# MCU.net
KiCad netlist of a schematic drawn in Altium Designer
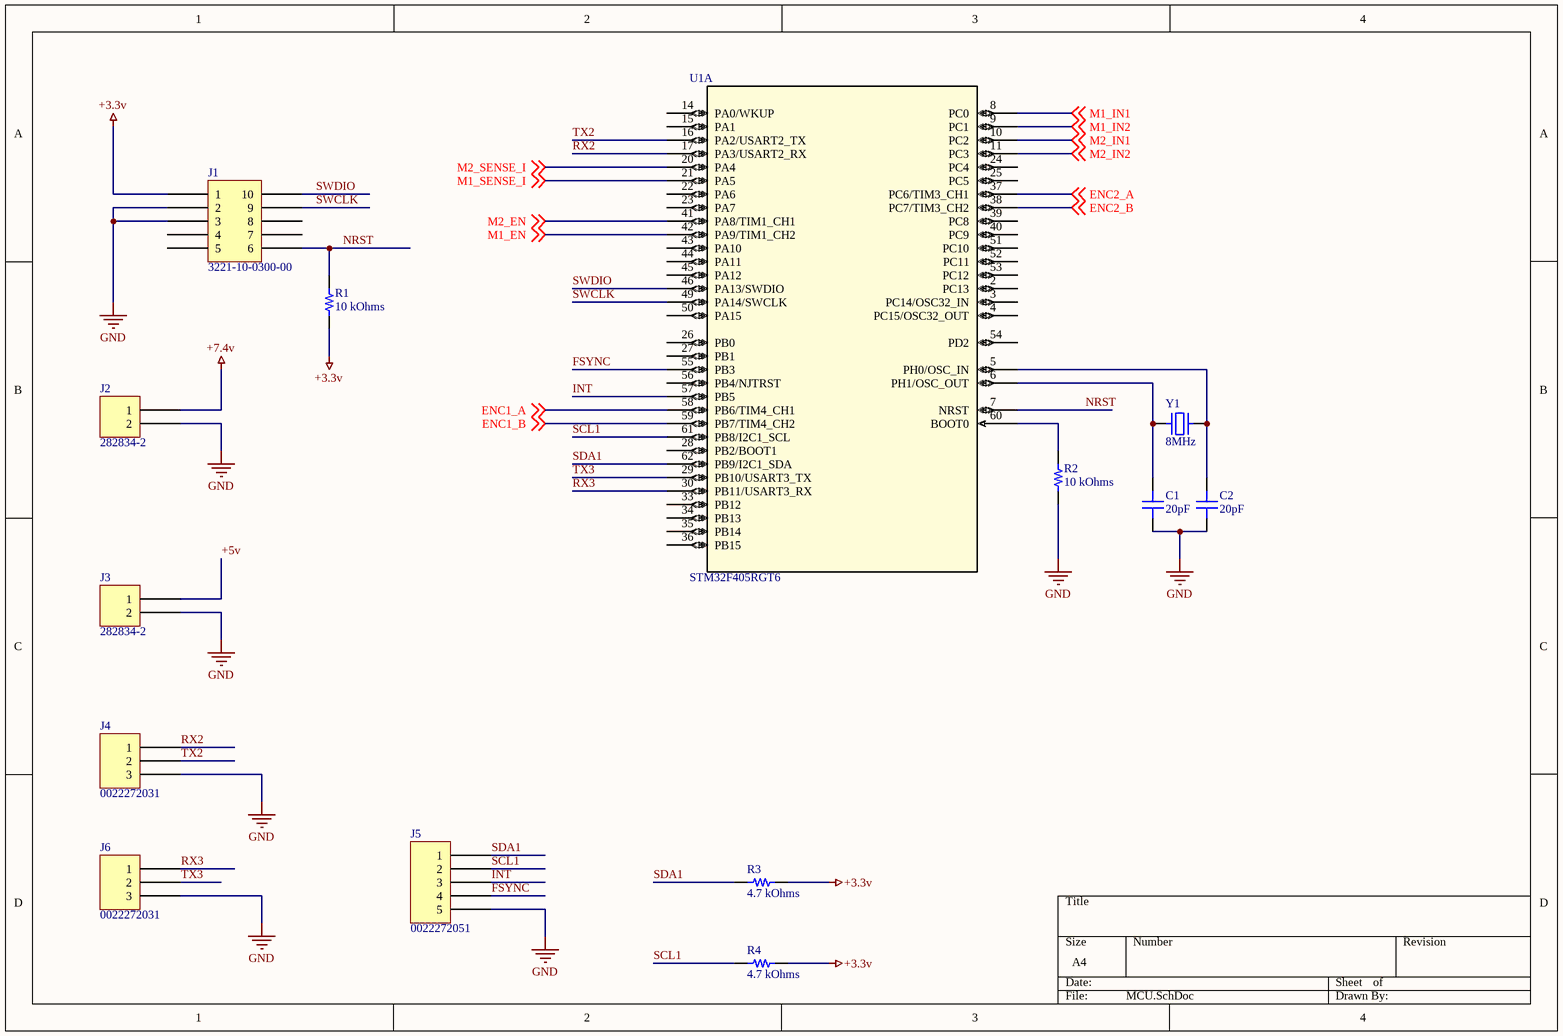
[diagram p0: MCU.SchDoc]

(export (version "E")
  (design (tool "Eeschema 10.0.6"))
  (components
    (comp (ref "C1")
      (value "20pF")
      (footprint "CAP 0805_2012")
      (description "CAP CER 20PF 16V C0G/NP0 0805")
      (fields (field (name "PART NUMBER") "C0805C200J4GAC7800") (field (name "MANUFACTURER") "KEMET"))
      (libsource (lib "Celestial Altium Library - altium_library") (part "Capacitor"))
    )
    (comp (ref "C2")
      (value "20pF")
      (footprint "CAP 0805_2012")
      (description "CAP CER 20PF 16V C0G/NP0 0805")
      (fields (field (name "PART NUMBER") "C0805C200J4GAC7800") (field (name "MANUFACTURER") "KEMET"))
      (libsource (lib "Celestial Altium Library - altium_library") (part "Capacitor"))
    )
    (comp (ref "J1")
      (value "3221-10-0300-00")
      (footprint "CNC TECH 3221-10-0300-00")
      (description "CONN HEADER SMD 10POS 1.27MM")
      (fields (field (name "MANUFACTURER") "CNC Tech"))
      (libsource (lib "Celestial Altium Library - altium_library") (part "2x5 Pin"))
    )
    (comp (ref "J2")
      (value "282834-2")
      (footprint "TE 282834-2")
      (description "TERM BLK 2P SIDE ENT 2.54MM PCB")
      (fields (field (name "MANUFACTURER") "TE Connectivity AMP Connectors") (field (name "VOLTAGE") "150V"))
      (libsource (lib "Celestial Altium Library - altium_library") (part "2 Pin"))
    )
    (comp (ref "J3")
      (value "282834-2")
      (footprint "TE 282834-2")
      (description "TERM BLK 2P SIDE ENT 2.54MM PCB")
      (fields (field (name "MANUFACTURER") "TE Connectivity AMP Connectors") (field (name "VOLTAGE") "150V"))
      (libsource (lib "Celestial Altium Library - altium_library") (part "2 Pin"))
    )
    (comp (ref "J4")
      (value "0022272031")
      (footprint "MOLEX KK 0022272031")
      (description "CONN HEADER VERT 3POS 2.54MM")
      (fields (field (name "MANUFACTURER") "Molex"))
      (libsource (lib "Celestial Altium Library - altium_library") (part "3 Pin"))
    )
    (comp (ref "J5")
      (value "0022272051")
      (footprint "MOLEX KK 0022272051")
      (description "CONN HEADER VERT 5POS 2.54MM")
      (fields (field (name "MANUFACTURER") "Molex"))
      (libsource (lib "Celestial Altium Library - altium_library") (part "5 Pin"))
    )
    (comp (ref "J6")
      (value "0022272031")
      (footprint "MOLEX KK 0022272031")
      (description "CONN HEADER VERT 3POS 2.54MM")
      (fields (field (name "MANUFACTURER") "Molex"))
      (libsource (lib "Celestial Altium Library - altium_library") (part "3 Pin"))
    )
    (comp (ref "R1")
      (value "10 kOhms")
      (footprint "RES 0805_2012")
      (description "RES 10K OHM 5% 1/8W 0805")
      (fields
        (field (name "PART NUMBER") "RMCS0805JT10K0")
        (field (name "MANUFACTURER") "Stackpole Electronics Inc")
      )
      (libsource (lib "Celestial Altium Library - altium_library") (part "Resistor"))
    )
    (comp (ref "R2")
      (value "10 kOhms")
      (footprint "RES 0805_2012")
      (description "RES SMD 10K OHM 5% 1/8W 0805")
      (fields (field (name "PART NUMBER") "RC0805JR-0710KL") (field (name "MANUFACTURER") "Yageo"))
      (libsource (lib "Celestial Altium Library - altium_library") (part "Resistor"))
    )
    (comp (ref "R3")
      (value "4.7 kOhms")
      (footprint "RES 0805_2012")
      (description "RES SMD 4.7K OHM 5% 1/8W 0805")
      (fields (field (name "PART NUMBER") "CRCW08054K70JNTA") (field (name "MANUFACTURER") "Vishay Dale"))
      (libsource (lib "Celestial Altium Library - altium_library") (part "Resistor"))
    )
    (comp (ref "R4")
      (value "4.7 kOhms")
      (footprint "RES 0805_2012")
      (description "RES SMD 4.7K OHM 5% 1/8W 0805")
      (fields (field (name "PART NUMBER") "CRCW08054K70JNTA") (field (name "MANUFACTURER") "Vishay Dale"))
      (libsource (lib "Celestial Altium Library - altium_library") (part "Resistor"))
    )
    (comp (ref "U1")
      (value "STM32F405RGT6")
      (footprint "LQFP64-10x10mm")
      (description "No Description Available")
      (fields (field (name "COPYRIGHT") "Copyright (C) 2018 Accelerated Designs. All rights reserved"))
      (libsource (lib "STM32F405RGT6") (part "STM32F405RGT6"))
    )
    (comp (ref "Y1")
      (value "8MHz")
      (footprint "NDK NX5032GA")
      (description "CRYSTAL 8MHZ 18PF SMD")
      (fields
        (field (name "PART NUMBER") "NX5032GA-8MHZ-EXS00A-CG07039")
        (field (name "MANUFACTURER") "NDK America, Inc.")
      )
      (libsource (lib "Celestial Altium Library - altium_library") (part "NDK Crystal NX5032GA"))
    )
  )
  (nets
    (net (code "1") (name "+3.3v") (class "Default")
      (node (ref "J1") (pin "1") (pinfunction "1_1") (pintype "passive"))
      (node (ref "R1") (pin "2") (pinfunction "2_2") (pintype "passive"))
      (node (ref "R3") (pin "2") (pinfunction "2_2") (pintype "passive"))
      (node (ref "R4") (pin "2") (pinfunction "2_2") (pintype "passive"))
    )
    (net (code "2") (name "+7.4v") (class "Default")
      (node (ref "J2") (pin "1") (pinfunction "1_1") (pintype "passive"))
    )
    (net (code "3") (name "/+5v") (class "Default")
      (node (ref "J3") (pin "1") (pinfunction "1_1") (pintype "passive"))
    )
    (net (code "4") (name "/FSYNC") (class "Default")
      (node (ref "J5") (pin "4") (pinfunction "4_4") (pintype "passive"))
      (node (ref "U1") (pin "55") (pinfunction "PB3_55") (pintype "bidirectional"))
    )
    (net (code "5") (name "/INT") (class "Default")
      (node (ref "J5") (pin "3") (pinfunction "3_3") (pintype "passive"))
      (node (ref "U1") (pin "57") (pinfunction "PB5_57") (pintype "bidirectional"))
    )
    (net (code "6") (name "/NRST") (class "Default")
      (node (ref "J1") (pin "6") (pinfunction "6_6") (pintype "passive"))
      (node (ref "R1") (pin "1") (pinfunction "1_1") (pintype "passive"))
      (node (ref "U1") (pin "7") (pinfunction "NRST_7") (pintype "bidirectional"))
    )
    (net (code "7") (name "/RX2") (class "Default")
      (node (ref "J4") (pin "1") (pinfunction "1_1") (pintype "passive"))
      (node (ref "U1") (pin "17") (pinfunction "PA3/USART2_RX_17") (pintype "bidirectional"))
    )
    (net (code "8") (name "/RX3") (class "Default")
      (node (ref "J6") (pin "1") (pinfunction "1_1") (pintype "passive"))
      (node (ref "U1") (pin "30") (pinfunction "PB11/USART3_RX_30") (pintype "bidirectional"))
    )
    (net (code "9") (name "/SCL1") (class "Default")
      (node (ref "J5") (pin "2") (pinfunction "2_2") (pintype "passive"))
      (node (ref "R4") (pin "1") (pinfunction "1_1") (pintype "passive"))
      (node (ref "U1") (pin "61") (pinfunction "PB8/I2C1_SCL_61") (pintype "bidirectional"))
    )
    (net (code "10") (name "/SDA1") (class "Default")
      (node (ref "J5") (pin "1") (pinfunction "1_1") (pintype "passive"))
      (node (ref "R3") (pin "1") (pinfunction "1_1") (pintype "passive"))
      (node (ref "U1") (pin "62") (pinfunction "PB9/I2C1_SDA_62") (pintype "bidirectional"))
    )
    (net (code "11") (name "/SWCLK") (class "Default")
      (node (ref "J1") (pin "9") (pinfunction "9_9") (pintype "passive"))
      (node (ref "U1") (pin "49") (pinfunction "PA14/SWCLK_49") (pintype "bidirectional"))
    )
    (net (code "12") (name "/SWDIO") (class "Default")
      (node (ref "J1") (pin "10") (pinfunction "10_10") (pintype "passive"))
      (node (ref "U1") (pin "46") (pinfunction "PA13/SWDIO_46") (pintype "bidirectional"))
    )
    (net (code "13") (name "/TX2") (class "Default")
      (node (ref "J4") (pin "2") (pinfunction "2_2") (pintype "passive"))
      (node (ref "U1") (pin "16") (pinfunction "PA2/USART2_TX_16") (pintype "bidirectional"))
    )
    (net (code "14") (name "/TX3") (class "Default")
      (node (ref "J6") (pin "2") (pinfunction "2_2") (pintype "passive"))
      (node (ref "U1") (pin "29") (pinfunction "PB10/USART3_TX_29") (pintype "bidirectional"))
    )
    (net (code "15") (name "ENC1_A") (class "Default")
      (node (ref "U1") (pin "58") (pinfunction "PB6/TIM4_CH1_58") (pintype "bidirectional"))
    )
    (net (code "16") (name "ENC1_B") (class "Default")
      (node (ref "U1") (pin "59") (pinfunction "PB7/TIM4_CH2_59") (pintype "bidirectional"))
    )
    (net (code "17") (name "ENC2_A") (class "Default")
      (node (ref "U1") (pin "37") (pinfunction "PC6/TIM3_CH1_37") (pintype "bidirectional"))
    )
    (net (code "18") (name "ENC2_B") (class "Default")
      (node (ref "U1") (pin "38") (pinfunction "PC7/TIM3_CH2_38") (pintype "bidirectional"))
    )
    (net (code "19") (name "GND") (class "Default")
      (node (ref "C1") (pin "1") (pinfunction "1_1") (pintype "passive"))
      (node (ref "C2") (pin "1") (pinfunction "1_1") (pintype "passive"))
      (node (ref "J1") (pin "2") (pinfunction "2_2") (pintype "passive"))
      (node (ref "J1") (pin "3") (pinfunction "3_3") (pintype "passive"))
      (node (ref "J2") (pin "2") (pinfunction "2_2") (pintype "passive"))
      (node (ref "J3") (pin "2") (pinfunction "2_2") (pintype "passive"))
      (node (ref "J4") (pin "3") (pinfunction "3_3") (pintype "passive"))
      (node (ref "J5") (pin "5") (pinfunction "5_5") (pintype "passive"))
      (node (ref "J6") (pin "3") (pinfunction "3_3") (pintype "passive"))
      (node (ref "R2") (pin "1") (pinfunction "1_1") (pintype "passive"))
    )
    (net (code "20") (name "M1_EN") (class "Default")
      (node (ref "U1") (pin "42") (pinfunction "PA9/TIM1_CH2_42") (pintype "bidirectional"))
    )
    (net (code "21") (name "M1_IN1") (class "Default")
      (node (ref "U1") (pin "8") (pinfunction "PC0_8") (pintype "bidirectional"))
    )
    (net (code "22") (name "M1_IN2") (class "Default")
      (node (ref "U1") (pin "9") (pinfunction "PC1_9") (pintype "bidirectional"))
    )
    (net (code "23") (name "M1_SENSE_I") (class "Default")
      (node (ref "U1") (pin "21") (pinfunction "PA5_21") (pintype "bidirectional"))
    )
    (net (code "24") (name "M2_EN") (class "Default")
      (node (ref "U1") (pin "41") (pinfunction "PA8/TIM1_CH1_41") (pintype "bidirectional"))
    )
    (net (code "25") (name "M2_IN1") (class "Default")
      (node (ref "U1") (pin "10") (pinfunction "PC2_10") (pintype "bidirectional"))
    )
    (net (code "26") (name "M2_IN2") (class "Default")
      (node (ref "U1") (pin "11") (pinfunction "PC3_11") (pintype "bidirectional"))
    )
    (net (code "27") (name "M2_SENSE_I") (class "Default")
      (node (ref "U1") (pin "20") (pinfunction "PA4_20") (pintype "bidirectional"))
    )
    (net (code "28") (name "Net-(U1A-BOOT0)") (class "Default")
      (node (ref "R2") (pin "2") (pinfunction "2_2") (pintype "passive"))
      (node (ref "U1") (pin "60") (pinfunction "BOOT0_60") (pintype "input"))
    )
    (net (code "29") (name "Net-(U1A-PH0{slash}OSC_IN)") (class "Default")
      (node (ref "C2") (pin "2") (pinfunction "2_2") (pintype "passive"))
      (node (ref "U1") (pin "5") (pinfunction "PH0/OSC_IN_5") (pintype "bidirectional"))
      (node (ref "Y1") (pin "2") (pinfunction "2_2") (pintype "passive"))
    )
    (net (code "30") (name "Net-(U1A-PH1{slash}OSC_OUT)") (class "Default")
      (node (ref "C1") (pin "2") (pinfunction "2_2") (pintype "passive"))
      (node (ref "U1") (pin "6") (pinfunction "PH1/OSC_OUT_6") (pintype "bidirectional"))
      (node (ref "Y1") (pin "1") (pinfunction "1_1") (pintype "passive"))
    )
    (net (code "31") (name "unconnected-(J1-Pad4)") (class "Default")
      (node (ref "J1") (pin "4") (pinfunction "4_4") (pintype "passive"))
    )
    (net (code "32") (name "unconnected-(J1-Pad5)") (class "Default")
      (node (ref "J1") (pin "5") (pinfunction "5_5") (pintype "passive"))
    )
    (net (code "33") (name "unconnected-(J1-Pad7)") (class "Default")
      (node (ref "J1") (pin "7") (pinfunction "7_7") (pintype "passive"))
    )
    (net (code "34") (name "unconnected-(J1-Pad8)") (class "Default")
      (node (ref "J1") (pin "8") (pinfunction "8_8") (pintype "passive"))
    )
    (net (code "35") (name "unconnected-(U1A-PA0{slash}WKUP-Pad14)") (class "Default")
      (node (ref "U1") (pin "14") (pinfunction "PA0/WKUP_14") (pintype "bidirectional"))
    )
    (net (code "36") (name "unconnected-(U1A-PA1-Pad15)") (class "Default")
      (node (ref "U1") (pin "15") (pinfunction "PA1_15") (pintype "bidirectional"))
    )
    (net (code "37") (name "unconnected-(U1A-PA6-Pad22)") (class "Default")
      (node (ref "U1") (pin "22") (pinfunction "PA6_22") (pintype "bidirectional"))
    )
    (net (code "38") (name "unconnected-(U1A-PA7-Pad23)") (class "Default")
      (node (ref "U1") (pin "23") (pinfunction "PA7_23") (pintype "bidirectional"))
    )
    (net (code "39") (name "unconnected-(U1A-PA10-Pad43)") (class "Default")
      (node (ref "U1") (pin "43") (pinfunction "PA10_43") (pintype "bidirectional"))
    )
    (net (code "40") (name "unconnected-(U1A-PA11-Pad44)") (class "Default")
      (node (ref "U1") (pin "44") (pinfunction "PA11_44") (pintype "bidirectional"))
    )
    (net (code "41") (name "unconnected-(U1A-PA12-Pad45)") (class "Default")
      (node (ref "U1") (pin "45") (pinfunction "PA12_45") (pintype "bidirectional"))
    )
    (net (code "42") (name "unconnected-(U1A-PA15-Pad50)") (class "Default")
      (node (ref "U1") (pin "50") (pinfunction "PA15_50") (pintype "bidirectional"))
    )
    (net (code "43") (name "unconnected-(U1A-PB0-Pad26)") (class "Default")
      (node (ref "U1") (pin "26") (pinfunction "PB0_26") (pintype "bidirectional"))
    )
    (net (code "44") (name "unconnected-(U1A-PB1-Pad27)") (class "Default")
      (node (ref "U1") (pin "27") (pinfunction "PB1_27") (pintype "bidirectional"))
    )
    (net (code "45") (name "unconnected-(U1A-PB2{slash}BOOT1-Pad28)") (class "Default")
      (node (ref "U1") (pin "28") (pinfunction "PB2/BOOT1_28") (pintype "bidirectional"))
    )
    (net (code "46") (name "unconnected-(U1A-PB4{slash}NJTRST-Pad56)") (class "Default")
      (node (ref "U1") (pin "56") (pinfunction "PB4/NJTRST_56") (pintype "bidirectional"))
    )
    (net (code "47") (name "unconnected-(U1A-PB12-Pad33)") (class "Default")
      (node (ref "U1") (pin "33") (pinfunction "PB12_33") (pintype "bidirectional"))
    )
    (net (code "48") (name "unconnected-(U1A-PB13-Pad34)") (class "Default")
      (node (ref "U1") (pin "34") (pinfunction "PB13_34") (pintype "bidirectional"))
    )
    (net (code "49") (name "unconnected-(U1A-PB14-Pad35)") (class "Default")
      (node (ref "U1") (pin "35") (pinfunction "PB14_35") (pintype "bidirectional"))
    )
    (net (code "50") (name "unconnected-(U1A-PB15-Pad36)") (class "Default")
      (node (ref "U1") (pin "36") (pinfunction "PB15_36") (pintype "bidirectional"))
    )
    (net (code "51") (name "unconnected-(U1A-PC4-Pad24)") (class "Default")
      (node (ref "U1") (pin "24") (pinfunction "PC4_24") (pintype "bidirectional"))
    )
    (net (code "52") (name "unconnected-(U1A-PC5-Pad25)") (class "Default")
      (node (ref "U1") (pin "25") (pinfunction "PC5_25") (pintype "bidirectional"))
    )
    (net (code "53") (name "unconnected-(U1A-PC8-Pad39)") (class "Default")
      (node (ref "U1") (pin "39") (pinfunction "PC8_39") (pintype "bidirectional"))
    )
    (net (code "54") (name "unconnected-(U1A-PC9-Pad40)") (class "Default")
      (node (ref "U1") (pin "40") (pinfunction "PC9_40") (pintype "bidirectional"))
    )
    (net (code "55") (name "unconnected-(U1A-PC10-Pad51)") (class "Default")
      (node (ref "U1") (pin "51") (pinfunction "PC10_51") (pintype "bidirectional"))
    )
    (net (code "56") (name "unconnected-(U1A-PC11-Pad52)") (class "Default")
      (node (ref "U1") (pin "52") (pinfunction "PC11_52") (pintype "bidirectional"))
    )
    (net (code "57") (name "unconnected-(U1A-PC12-Pad53)") (class "Default")
      (node (ref "U1") (pin "53") (pinfunction "PC12_53") (pintype "bidirectional"))
    )
    (net (code "58") (name "unconnected-(U1A-PC13-Pad2)") (class "Default")
      (node (ref "U1") (pin "2") (pinfunction "PC13_2") (pintype "bidirectional"))
    )
    (net (code "59") (name "unconnected-(U1A-PC14{slash}OSC32_IN-Pad3)") (class "Default")
      (node (ref "U1") (pin "3") (pinfunction "PC14/OSC32_IN_3") (pintype "bidirectional"))
    )
    (net (code "60") (name "unconnected-(U1A-PC15{slash}OSC32_OUT-Pad4)") (class "Default")
      (node (ref "U1") (pin "4") (pinfunction "PC15/OSC32_OUT_4") (pintype "bidirectional"))
    )
    (net (code "61") (name "unconnected-(U1A-PD2-Pad54)") (class "Default")
      (node (ref "U1") (pin "54") (pinfunction "PD2_54") (pintype "bidirectional"))
    )
  )
)
